# BuckCircuit.net
KiCad netlist of a schematic drawn in Altium Designer
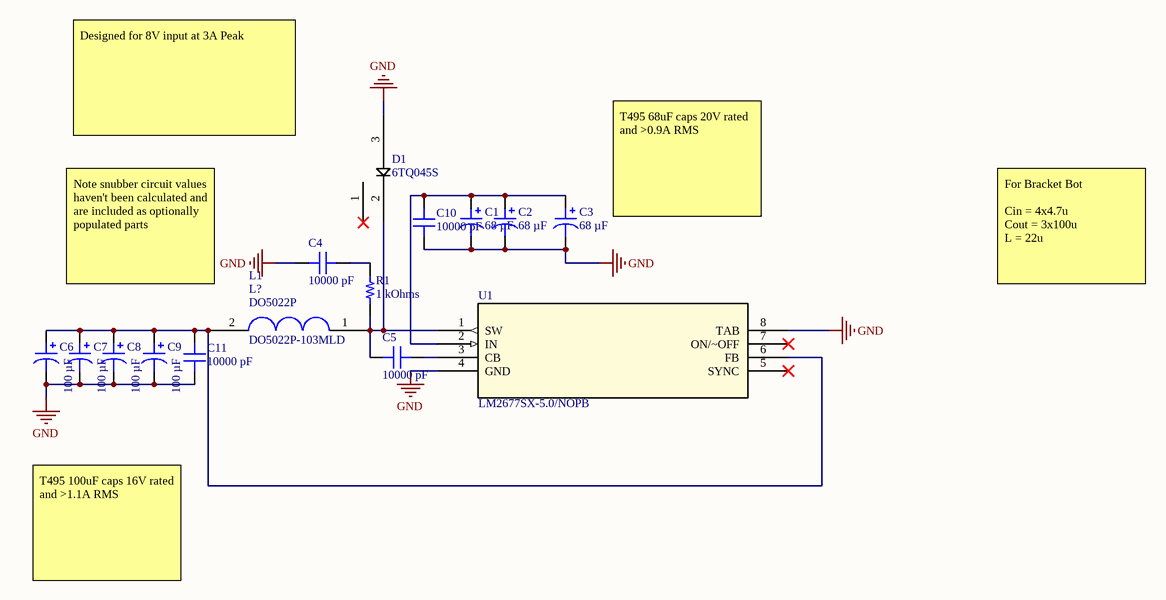
[diagram p0: BuckCircuit.SchDoc]

(export (version "E")
  (design (tool "Eeschema 10.0.6"))
  (components
    (comp (ref "C1")
      (value "68 µF")
      (footprint "CAP POL 2917_7343")
      (description "CAP TANT 68UF 10% 20V 2917")
      (fields (field (name "PART NUMBER") "T495D686K020ATE150") (field (name "MANUFACTURER") "KEMET"))
      (libsource (lib "Celestial Altium Library - altium_library") (part "Polarised Capacitor"))
    )
    (comp (ref "C2")
      (value "68 µF")
      (footprint "CAP POL 2917_7343")
      (description "CAP TANT 68UF 10% 20V 2917")
      (fields (field (name "PART NUMBER") "T495D686K020ATE150") (field (name "MANUFACTURER") "KEMET"))
      (libsource (lib "Celestial Altium Library - altium_library") (part "Polarised Capacitor"))
    )
    (comp (ref "C3")
      (value "68 µF")
      (footprint "CAP POL 2917_7343")
      (description "CAP TANT 68UF 10% 20V 2917")
      (fields (field (name "PART NUMBER") "T495D686K020ATE150") (field (name "MANUFACTURER") "KEMET"))
      (libsource (lib "Celestial Altium Library - altium_library") (part "Polarised Capacitor"))
    )
    (comp (ref "C4")
      (value "10000 pF")
      (footprint "CAP 0805_2012")
      (description "CAP CER 10000PF 50V X7R 0805")
      (fields (field (name "PART NUMBER") "C0805X103J5RACAUTO") (field (name "MANUFACTURER") "KEMET"))
      (libsource (lib "Celestial Altium Library - altium_library") (part "Capacitor"))
    )
    (comp (ref "C5")
      (value "10000 pF")
      (footprint "CAP 0805_2012")
      (description "CAP CER 10000PF 50V X7R 0805")
      (fields (field (name "PART NUMBER") "C0805X103J5RACAUTO") (field (name "MANUFACTURER") "KEMET"))
      (libsource (lib "Celestial Altium Library - altium_library") (part "Capacitor"))
    )
    (comp (ref "C6")
      (value "100 µF")
      (footprint "CAP POL 2917_7343")
      (description "CAP TANT 100UF 20% 16V 2917")
      (fields (field (name "PART NUMBER") "T495D107M016ATE100") (field (name "MANUFACTURER") "KEMET"))
      (libsource (lib "Celestial Altium Library - altium_library") (part "Polarised Capacitor"))
    )
    (comp (ref "C7")
      (value "100 µF")
      (footprint "CAP POL 2917_7343")
      (description "CAP TANT 100UF 20% 16V 2917")
      (fields (field (name "PART NUMBER") "T495D107M016ATE100") (field (name "MANUFACTURER") "KEMET"))
      (libsource (lib "Celestial Altium Library - altium_library") (part "Polarised Capacitor"))
    )
    (comp (ref "C8")
      (value "100 µF")
      (footprint "CAP POL 2917_7343")
      (description "CAP TANT 100UF 20% 16V 2917")
      (fields (field (name "PART NUMBER") "T495D107M016ATE100") (field (name "MANUFACTURER") "KEMET"))
      (libsource (lib "Celestial Altium Library - altium_library") (part "Polarised Capacitor"))
    )
    (comp (ref "C9")
      (value "100 µF")
      (footprint "CAP POL 2917_7343")
      (description "CAP TANT 100UF 20% 16V 2917")
      (fields (field (name "PART NUMBER") "T495D107M016ATE100") (field (name "MANUFACTURER") "KEMET"))
      (libsource (lib "Celestial Altium Library - altium_library") (part "Polarised Capacitor"))
    )
    (comp (ref "C10")
      (value "10000 pF")
      (footprint "CAP 0805_2012")
      (description "CAP CER 10000PF 50V X7R 0805")
      (fields (field (name "PART NUMBER") "C0805X103J5RACAUTO") (field (name "MANUFACTURER") "KEMET"))
      (libsource (lib "Celestial Altium Library - altium_library") (part "Capacitor"))
    )
    (comp (ref "C11")
      (value "10000 pF")
      (footprint "CAP 0805_2012")
      (description "CAP CER 10000PF 50V X7R 0805")
      (fields (field (name "PART NUMBER") "C0805X103J5RACAUTO") (field (name "MANUFACTURER") "KEMET"))
      (libsource (lib "Celestial Altium Library - altium_library") (part "Capacitor"))
    )
    (comp (ref "D1")
      (value "6TQ045S")
      (footprint "DPAK 6TQ045S")
      (libsource (lib "2020-09-26_17-27-19") (part "6TQ045S"))
    )
    (comp (ref "L1")
      (value "DO5022P-103MLD")
      (footprint "DO5022P-103MLD")
      (libsource (lib "2020-09-26_17-27-19") (part "DO5022P-103MLD"))
    )
    (comp (ref "R1")
      (value "1 kOhms")
      (footprint "RES 0603_1608")
      (description "RES SMD 1K OHM 0.1% 1/16W 0603")
      (fields
        (field (name "PART NUMBER") "CPF0603B1K0E")
        (field (name "MANUFACTURER") "TE Connectivity Passive Product")
      )
      (libsource (lib "Celestial Altium Library - altium_library") (part "Resistor"))
    )
    (comp (ref "U1")
      (value "LM2677SX-5.0/NOPB")
      (footprint "TS7B")
      (description "No Description Available")
      (fields (field (name "COPYRIGHT") "Copyright (C) 2022 Ultra Librarian. All rights reserved."))
      (libsource (lib "2020-09-26_17-27-19") (part "LM2677SX-5.0/NOPB"))
    )
  )
  (nets
    (net (code "1") (name "GND") (class "Default")
      (node (ref "C1") (pin "2") (pinfunction "2_2") (pintype "passive"))
      (node (ref "C10") (pin "1") (pinfunction "1_1") (pintype "passive"))
      (node (ref "C11") (pin "1") (pinfunction "1_1") (pintype "passive"))
      (node (ref "C2") (pin "2") (pinfunction "2_2") (pintype "passive"))
      (node (ref "C3") (pin "2") (pinfunction "2_2") (pintype "passive"))
      (node (ref "C4") (pin "2") (pinfunction "2_2") (pintype "passive"))
      (node (ref "C6") (pin "2") (pinfunction "2_2") (pintype "passive"))
      (node (ref "C7") (pin "2") (pinfunction "2_2") (pintype "passive"))
      (node (ref "C8") (pin "2") (pinfunction "2_2") (pintype "passive"))
      (node (ref "C9") (pin "2") (pinfunction "2_2") (pintype "passive"))
      (node (ref "D1") (pin "3") (pintype "passive"))
      (node (ref "U1") (pin "4") (pinfunction "GND_4") (pintype "passive"))
      (node (ref "U1") (pin "8") (pinfunction "TAB_8") (pintype "passive"))
    )
    (net (code "2") (name "Net-(C4-Pad1)") (class "Default")
      (node (ref "C4") (pin "1") (pinfunction "1_1") (pintype "passive"))
      (node (ref "R1") (pin "2") (pinfunction "2_2") (pintype "passive"))
    )
    (net (code "3") (name "Net-(U1-CB)") (class "Default")
      (node (ref "C5") (pin "2") (pinfunction "2_2") (pintype "passive"))
      (node (ref "U1") (pin "3") (pinfunction "CB_3") (pintype "passive"))
    )
    (net (code "4") (name "Net-(U1-FB)") (class "Default")
      (node (ref "C11") (pin "2") (pinfunction "2_2") (pintype "passive"))
      (node (ref "C6") (pin "1") (pinfunction "1_1") (pintype "passive"))
      (node (ref "C7") (pin "1") (pinfunction "1_1") (pintype "passive"))
      (node (ref "C8") (pin "1") (pinfunction "1_1") (pintype "passive"))
      (node (ref "C9") (pin "1") (pinfunction "1_1") (pintype "passive"))
      (node (ref "L1") (pin "2") (pintype "passive"))
      (node (ref "U1") (pin "6") (pinfunction "FB_6") (pintype "passive"))
    )
    (net (code "5") (name "Net-(U1-IN)") (class "Default")
      (node (ref "C1") (pin "1") (pinfunction "1_1") (pintype "passive"))
      (node (ref "C10") (pin "2") (pinfunction "2_2") (pintype "passive"))
      (node (ref "C2") (pin "1") (pinfunction "1_1") (pintype "passive"))
      (node (ref "C3") (pin "1") (pinfunction "1_1") (pintype "passive"))
      (node (ref "U1") (pin "2") (pinfunction "IN_2") (pintype "input"))
    )
    (net (code "6") (name "Net-(U1-SW)") (class "Default")
      (node (ref "C5") (pin "1") (pinfunction "1_1") (pintype "passive"))
      (node (ref "D1") (pin "2") (pintype "passive"))
      (node (ref "L1") (pin "1") (pintype "passive"))
      (node (ref "R1") (pin "1") (pinfunction "1_1") (pintype "passive"))
      (node (ref "U1") (pin "1") (pinfunction "SW_1") (pintype "output"))
    )
    (net (code "7") (name "unconnected-(D1-Pad1)") (class "Default")
      (node (ref "D1") (pin "1") (pintype "passive+no_connect"))
    )
    (net (code "8") (name "unconnected-(U1-ON{slash}~OFF-Pad7)") (class "Default")
      (node (ref "U1") (pin "7") (pinfunction "ON/~OFF_7") (pintype "passive+no_connect"))
    )
    (net (code "9") (name "unconnected-(U1-SYNC-Pad5)") (class "Default")
      (node (ref "U1") (pin "5") (pinfunction "SYNC_5") (pintype "passive+no_connect"))
    )
  )
)
